# Timer_SHO.net
KiCad netlist of a schematic drawn in EAGLE
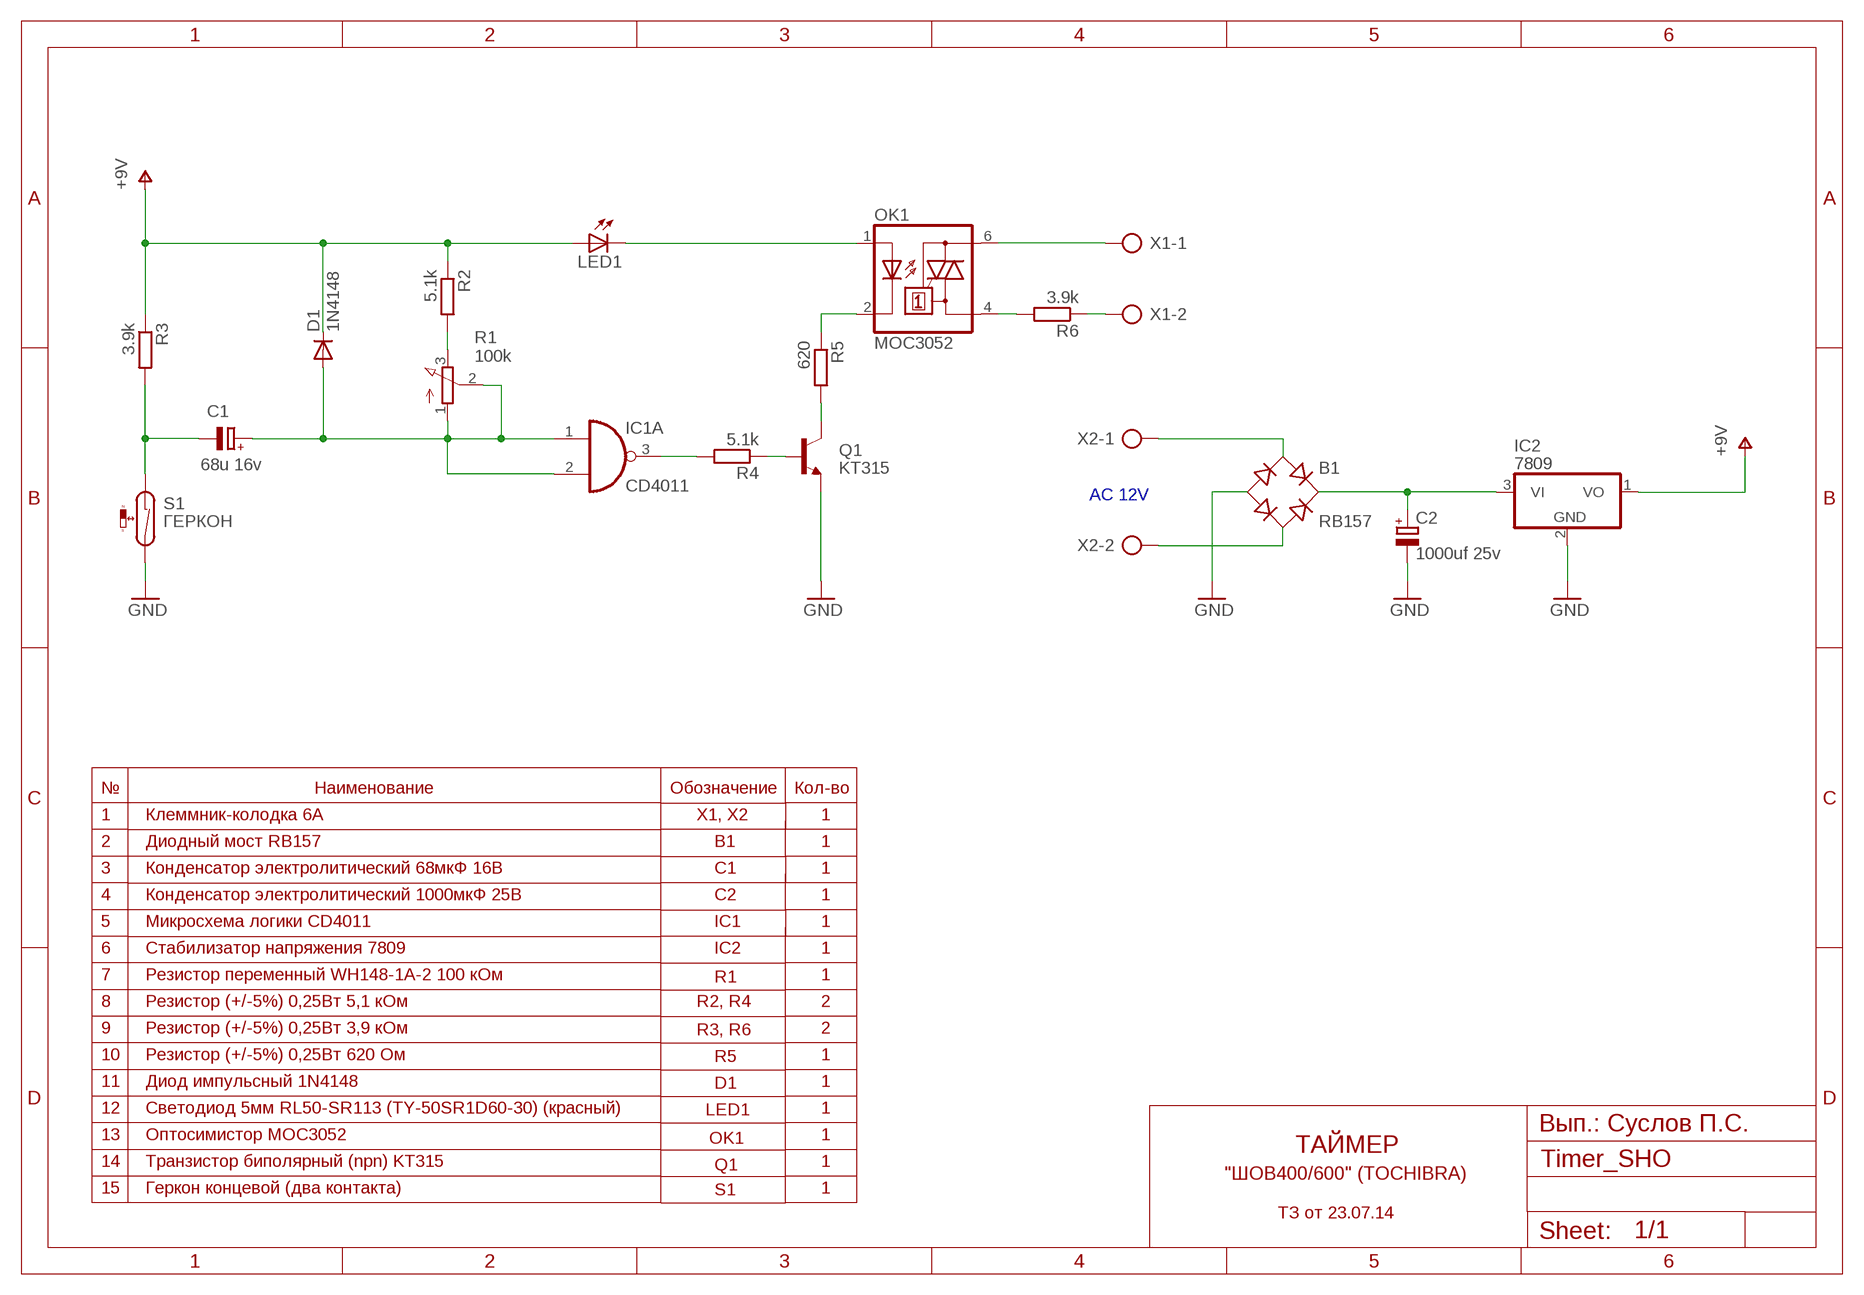
[diagram p0: schematic, sheet 1]

(export (version "E")
  (design (tool "Eeschema 10.0.6"))
  (components
    (comp (ref "B1")
      (value "RB157")
      (footprint "eagle-import:B-DIL")
      (libsource (lib "eagle-import") (part "B-DIL"))
    )
    (comp (ref "C1")
      (value "68u 16v")
      (footprint "eagle-import:085CS_1AR")
      (libsource (lib "eagle-import") (part "CPOL-EU085CS-1AR"))
    )
    (comp (ref "C2")
      (value "1000uf 25v")
      (footprint "eagle-import:085CS_1AR")
      (libsource (lib "eagle-import") (part "CPOL-EU085CS-1AR"))
    )
    (comp (ref "D1")
      (value "1N4148")
      (footprint "eagle-import:DO41-10")
      (libsource (lib "eagle-import") (part "1N4004"))
    )
    (comp (ref "IC1")
      (value "CD4011")
      (footprint "eagle-import:DIL14")
      (libsource (lib "eagle-import") (part "7400NAC"))
    )
    (comp (ref "IC2")
      (value "7809")
      (footprint "eagle-import:TO92")
      (libsource (lib "eagle-import") (part "78L08"))
    )
    (comp (ref "LED1")
      (value "LED5MM")
      (footprint "eagle-import:LED5MM")
      (libsource (lib "eagle-import") (part "LED5MM"))
    )
    (comp (ref "OK1")
      (value "MOC3052")
      (footprint "eagle-import:DIL06B")
      (libsource (lib "eagle-import") (part "MOC30T31"))
    )
    (comp (ref "Q1")
      (value "KT315")
      (footprint "eagle-import:TO92")
      (libsource (lib "eagle-import") (part "BC237"))
    )
    (comp (ref "R1")
      (value "100k")
      (footprint "eagle-import:3RP_1610N")
      (libsource (lib "eagle-import") (part "3RP/1610N"))
    )
    (comp (ref "R2")
      (value "5.1k")
      (footprint "eagle-import:0309_10")
      (libsource (lib "eagle-import") (part "R-EU_0309/10"))
    )
    (comp (ref "R3")
      (value "3.9k")
      (footprint "eagle-import:0309_10")
      (libsource (lib "eagle-import") (part "R-EU_0309/10"))
    )
    (comp (ref "R4")
      (value "5.1k")
      (footprint "eagle-import:0309_10")
      (libsource (lib "eagle-import") (part "R-EU_0309/10"))
    )
    (comp (ref "R5")
      (value "620")
      (footprint "eagle-import:0309_10")
      (libsource (lib "eagle-import") (part "R-EU_0309/10"))
    )
    (comp (ref "R6")
      (value "3.9k")
      (footprint "eagle-import:0309_10")
      (libsource (lib "eagle-import") (part "R-EU_0309/10"))
    )
    (comp (ref "S1")
      (value "ГЕРКОН")
      (footprint "eagle-import:CT10-A2")
      (libsource (lib "eagle-import") (part "REED-SWITCH-CT10-A2"))
    )
    (comp (ref "X1")
      (value "AK500/2")
      (footprint "eagle-import:AK500_2")
      (libsource (lib "eagle-import") (part "AK500/2"))
    )
    (comp (ref "X2")
      (value "AK500/2")
      (footprint "eagle-import:AK500_2")
      (libsource (lib "eagle-import") (part "AK500/2"))
    )
  )
  (nets
    (net (code "1") (name "+9V") (class "Default")
      (node (ref "D1") (pin "C") (pinfunction "C_C") (pintype "passive"))
      (node (ref "IC2") (pin "1") (pinfunction "VO_1") (pintype "passive"))
      (node (ref "LED1") (pin "A") (pinfunction "A_A") (pintype "passive"))
      (node (ref "R2") (pin "1") (pinfunction "1_1") (pintype "passive"))
      (node (ref "R3") (pin "1") (pinfunction "1_1") (pintype "passive"))
    )
    (net (code "2") (name "GND") (class "Default")
      (node (ref "B1") (pin "-") (pinfunction "-_-") (pintype "passive"))
      (node (ref "C2") (pin "-") (pinfunction "-_-") (pintype "passive"))
      (node (ref "IC2") (pin "2") (pinfunction "GND_2") (pintype "passive"))
      (node (ref "Q1") (pin "1") (pinfunction "E_1") (pintype "passive"))
      (node (ref "S1") (pin "2") (pinfunction "2_2") (pintype "passive"))
    )
    (net (code "3") (name "Net-(C1-Pad-)") (class "Default")
      (node (ref "C1") (pin "-") (pinfunction "-_-") (pintype "passive"))
      (node (ref "R3") (pin "2") (pinfunction "2_2") (pintype "passive"))
      (node (ref "S1") (pin "1") (pinfunction "1_1") (pintype "passive"))
    )
    (net (code "4") (name "Net-(IC1A-I0)") (class "Default")
      (node (ref "C1") (pin "+") (pinfunction "+_+") (pintype "passive"))
      (node (ref "D1") (pin "A") (pinfunction "A_A") (pintype "passive"))
      (node (ref "IC1") (pin "1") (pinfunction "I0_1") (pintype "input"))
      (node (ref "IC1") (pin "2") (pinfunction "I1_2") (pintype "input"))
      (node (ref "R1") (pin "1") (pinfunction "A_1") (pintype "passive"))
      (node (ref "R1") (pin "2") (pinfunction "S_2") (pintype "passive"))
    )
    (net (code "5") (name "Net-(IC1A-O)") (class "Default")
      (node (ref "IC1") (pin "3") (pinfunction "O_3") (pintype "output"))
      (node (ref "R4") (pin "2") (pinfunction "2_2") (pintype "passive"))
    )
    (net (code "6") (name "Net-(IC2-VI)") (class "Default")
      (node (ref "B1") (pin "+") (pinfunction "+_+") (pintype "passive"))
      (node (ref "C2") (pin "+") (pinfunction "+_+") (pintype "passive"))
      (node (ref "IC2") (pin "3") (pinfunction "VI_3") (pintype "input"))
    )
    (net (code "7") (name "Net-(LED1-C)") (class "Default")
      (node (ref "LED1") (pin "K") (pinfunction "C_K") (pintype "passive"))
      (node (ref "OK1") (pin "1") (pinfunction "A_1") (pintype "passive"))
    )
    (net (code "8") (name "Net-(OK1-A1)") (class "Default")
      (node (ref "OK1") (pin "4") (pinfunction "A1_4") (pintype "passive"))
      (node (ref "R6") (pin "2") (pinfunction "2_2") (pintype "passive"))
    )
    (net (code "9") (name "Net-(OK1-A2)") (class "Default")
      (node (ref "OK1") (pin "6") (pinfunction "A2_6") (pintype "passive"))
      (node (ref "X1") (pin "1") (pinfunction "KL_1") (pintype "passive"))
    )
    (net (code "10") (name "Net-(OK1-C)") (class "Default")
      (node (ref "OK1") (pin "2") (pinfunction "C_2") (pintype "passive"))
      (node (ref "R5") (pin "1") (pinfunction "1_1") (pintype "passive"))
    )
    (net (code "11") (name "Net-(Q1-B)") (class "Default")
      (node (ref "Q1") (pin "2") (pinfunction "B_2") (pintype "passive"))
      (node (ref "R4") (pin "1") (pinfunction "1_1") (pintype "passive"))
    )
    (net (code "12") (name "Net-(Q1-C)") (class "Default")
      (node (ref "Q1") (pin "3") (pinfunction "C_3") (pintype "passive"))
      (node (ref "R5") (pin "2") (pinfunction "2_2") (pintype "passive"))
    )
    (net (code "13") (name "Net-(R1-E)") (class "Default")
      (node (ref "R1") (pin "3") (pinfunction "E_3") (pintype "passive"))
      (node (ref "R2") (pin "2") (pinfunction "2_2") (pintype "passive"))
    )
    (net (code "14") (name "Net-(X1B-KL)") (class "Default")
      (node (ref "R6") (pin "1") (pinfunction "1_1") (pintype "passive"))
      (node (ref "X1") (pin "2") (pinfunction "KL_2") (pintype "passive"))
    )
    (net (code "15") (name "Net-(X2A-KL)") (class "Default")
      (node (ref "B1") (pin "AC1") (pinfunction "AC1_AC1") (pintype "passive"))
      (node (ref "X2") (pin "1") (pinfunction "KL_1") (pintype "passive"))
    )
    (net (code "16") (name "Net-(X2B-KL)") (class "Default")
      (node (ref "B1") (pin "AC2") (pinfunction "AC2_AC2") (pintype "passive"))
      (node (ref "X2") (pin "2") (pinfunction "KL_2") (pintype "passive"))
    )
  )
)
